# Control.net
KiCad netlist of a schematic drawn in Altium Designer
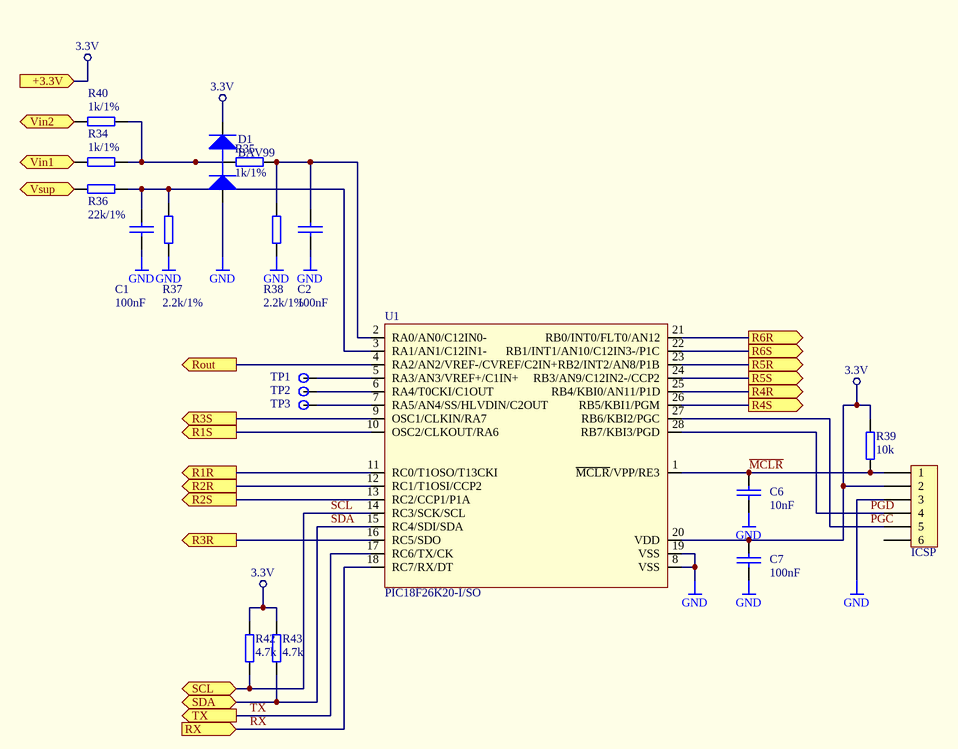
[diagram p0: Control.SchDoc]

(export (version "E")
  (design (tool "Eeschema 10.0.6"))
  (components
    (comp (ref "C1")
      (value "100nF")
      (footprint "0805_1")
      (description "Capacitor")
      (libsource (lib "*") (part "CAP"))
    )
    (comp (ref "C2")
      (value "100nF")
      (footprint "0805_1")
      (description "Capacitor")
      (libsource (lib "*") (part "CAP"))
    )
    (comp (ref "C6")
      (value "10nF")
      (footprint "0805_1")
      (description "Capacitor")
      (libsource (lib "*") (part "CAP"))
    )
    (comp (ref "C7")
      (value "100nF")
      (footprint "0805_1")
      (description "Capacitor")
      (libsource (lib "*") (part "CAP"))
    )
    (comp (ref "D1")
      (value "BAV99")
      (footprint "SOT-23")
      (description "SOT23 Silicon Planar High-Speed Switching Series Diode Pair")
      (fields
        (field (name "MANUFACTURER") "Zetex")
        (field (name "PUBLISHER") "Altium Hobart Technology Centre")
      )
      (libsource (lib "Zetex Discrete Diode") (part "BAV99"))
    )
    (comp (ref "ICSP")
      (value "CON6")
      (footprint "JP6")
      (description "Connector")
      (libsource (lib "*") (part "CON6"))
    )
    (comp (ref "R34")
      (value "1k/1%")
      (footprint "0805_1")
      (description "Resistor")
      (libsource (lib "*") (part "RES"))
    )
    (comp (ref "R35")
      (value "1k/1%")
      (footprint "0805_1")
      (description "Resistor")
      (libsource (lib "*") (part "RES"))
    )
    (comp (ref "R36")
      (value "22k/1%")
      (footprint "0805_1")
      (description "Resistor")
      (libsource (lib "*") (part "RES"))
    )
    (comp (ref "R37")
      (value "2.2k/1%")
      (footprint "0805_1")
      (description "Resistor")
      (libsource (lib "*") (part "RES"))
    )
    (comp (ref "R38")
      (value "2.2k/1%")
      (footprint "0805_1")
      (description "Resistor")
      (libsource (lib "*") (part "RES"))
    )
    (comp (ref "R39")
      (value "10k")
      (footprint "0805_1")
      (description "Resistor")
      (libsource (lib "*") (part "RES"))
    )
    (comp (ref "R40")
      (value "1k/1%")
      (footprint "0805_1")
      (description "Resistor")
      (libsource (lib "*") (part "RES"))
    )
    (comp (ref "R42")
      (value "4.7k")
      (footprint "0805_1")
      (description "Resistor")
      (libsource (lib "*") (part "RES"))
    )
    (comp (ref "R43")
      (value "4.7k")
      (footprint "0805_1")
      (description "Resistor")
      (libsource (lib "*") (part "RES"))
    )
    (comp (ref "TP1")
      (value "TESTPAD")
      (footprint "PAD-36/65")
      (libsource (lib "MainSchlib") (part "TESTPAD"))
    )
    (comp (ref "TP2")
      (value "TESTPAD")
      (footprint "PAD-36/65")
      (libsource (lib "MainSchlib") (part "TESTPAD"))
    )
    (comp (ref "TP3")
      (value "TESTPAD")
      (footprint "PAD-36/65")
      (libsource (lib "MainSchlib") (part "TESTPAD"))
    )
    (comp (ref "U1")
      (value "PIC18F26K20-I/SO")
      (footprint "SOIC-28")
      (description "PIC18 mid-range mcu")
      (libsource (lib "MainSchlib") (part "PIC18F26K20-I/SO"))
    )
  )
  (nets
    (net (code "1") (name "/PGC") (class "Default")
      (node (ref "ICSP") (pin "5") (pinfunction "5_5") (pintype "passive"))
      (node (ref "U1") (pin "27") (pinfunction "RB6/KBI2/PGC_27") (pintype "passive"))
    )
    (net (code "2") (name "/PGD") (class "Default")
      (node (ref "ICSP") (pin "4") (pinfunction "4_4") (pintype "passive"))
      (node (ref "U1") (pin "28") (pinfunction "RB7/KBI3/PGD_28") (pintype "passive"))
    )
    (net (code "3") (name "/R1R") (class "Default")
      (node (ref "U1") (pin "11") (pinfunction "RC0/T1OSO/T13CKI_11") (pintype "passive"))
    )
    (net (code "4") (name "/R1S") (class "Default")
      (node (ref "U1") (pin "10") (pinfunction "OSC2/CLKOUT/RA6_10") (pintype "passive"))
    )
    (net (code "5") (name "/R2R") (class "Default")
      (node (ref "U1") (pin "12") (pinfunction "RC1/T1OSI/CCP2_12") (pintype "passive"))
    )
    (net (code "6") (name "/R2S") (class "Default")
      (node (ref "U1") (pin "13") (pinfunction "RC2/CCP1/P1A_13") (pintype "passive"))
    )
    (net (code "7") (name "/R3R") (class "Default")
      (node (ref "U1") (pin "16") (pinfunction "RC5/SDO_16") (pintype "passive"))
    )
    (net (code "8") (name "/R3S") (class "Default")
      (node (ref "U1") (pin "9") (pinfunction "OSC1/CLKIN/RA7_9") (pintype "passive"))
    )
    (net (code "9") (name "/R4R") (class "Default")
      (node (ref "U1") (pin "25") (pinfunction "RB4/KBI0/AN11/P1D_25") (pintype "passive"))
    )
    (net (code "10") (name "/R4S") (class "Default")
      (node (ref "U1") (pin "26") (pinfunction "RB5/KBI1/PGM_26") (pintype "passive"))
    )
    (net (code "11") (name "/R5R") (class "Default")
      (node (ref "U1") (pin "23") (pinfunction "RB2/INT2/AN8/P1B_23") (pintype "passive"))
    )
    (net (code "12") (name "/R5S") (class "Default")
      (node (ref "U1") (pin "24") (pinfunction "RB3/AN9/C12IN2-/CCP2_24") (pintype "passive"))
    )
    (net (code "13") (name "/R6R") (class "Default")
      (node (ref "U1") (pin "21") (pinfunction "RB0/INT0/FLT0/AN12_21") (pintype "passive"))
    )
    (net (code "14") (name "/R6S") (class "Default")
      (node (ref "U1") (pin "22") (pinfunction "RB1/INT1/AN10/C12IN3-/P1C_22") (pintype "passive"))
    )
    (net (code "15") (name "/RX") (class "Default")
      (node (ref "U1") (pin "18") (pinfunction "RC7/RX/DT_18") (pintype "passive"))
    )
    (net (code "16") (name "/Rout") (class "Default")
      (node (ref "U1") (pin "4") (pinfunction "RA2/AN2/VREF-/CVREF/C2IN+_4") (pintype "passive"))
    )
    (net (code "17") (name "/SCL") (class "Default")
      (node (ref "R42") (pin "1") (pintype "passive"))
      (node (ref "U1") (pin "14") (pinfunction "RC3/SCK/SCL_14") (pintype "passive"))
    )
    (net (code "18") (name "/SDA") (class "Default")
      (node (ref "R43") (pin "1") (pintype "passive"))
      (node (ref "U1") (pin "15") (pinfunction "RC4/SDI/SDA_15") (pintype "passive"))
    )
    (net (code "19") (name "/TX") (class "Default")
      (node (ref "U1") (pin "17") (pinfunction "RC6/TX/CK_17") (pintype "passive"))
    )
    (net (code "20") (name "/Vin1") (class "Default") (node (ref "R34") (pin "2") (pintype "passive")))
    (net (code "21") (name "/Vin2") (class "Default") (node (ref "R40") (pin "2") (pintype "passive")))
    (net (code "22") (name "/Vsup") (class "Default") (node (ref "R36") (pin "2") (pintype "passive")))
    (net (code "23") (name "/~{MCLR}") (class "Default")
      (node (ref "C6") (pin "1") (pinfunction "1_1") (pintype "passive"))
      (node (ref "ICSP") (pin "1") (pinfunction "1_1") (pintype "passive"))
      (node (ref "R39") (pin "1") (pintype "passive"))
      (node (ref "U1") (pin "1") (pinfunction "~{MCLR}/VPP/RE3_1") (pintype "passive"))
    )
    (net (code "24") (name "3.3V") (class "Default")
      (node (ref "C7") (pin "1") (pinfunction "1_1") (pintype "passive"))
      (node (ref "D1") (pin "2") (pinfunction "K_2") (pintype "passive"))
      (node (ref "ICSP") (pin "2") (pinfunction "2_2") (pintype "passive"))
      (node (ref "R39") (pin "2") (pintype "passive"))
      (node (ref "R42") (pin "2") (pintype "passive"))
      (node (ref "R43") (pin "2") (pintype "passive"))
      (node (ref "U1") (pin "20") (pinfunction "VDD_20") (pintype "passive"))
    )
    (net (code "25") (name "GND") (class "Default")
      (node (ref "C1") (pin "2") (pinfunction "2_2") (pintype "passive"))
      (node (ref "C2") (pin "2") (pinfunction "2_2") (pintype "passive"))
      (node (ref "C6") (pin "2") (pinfunction "2_2") (pintype "passive"))
      (node (ref "C7") (pin "2") (pinfunction "2_2") (pintype "passive"))
      (node (ref "D1") (pin "1") (pinfunction "A_1") (pintype "passive"))
      (node (ref "ICSP") (pin "3") (pinfunction "3_3") (pintype "passive"))
      (node (ref "R37") (pin "1") (pintype "passive"))
      (node (ref "R38") (pin "1") (pintype "passive"))
      (node (ref "U1") (pin "19") (pinfunction "VSS_19") (pintype "passive"))
      (node (ref "U1") (pin "8") (pinfunction "VSS_8") (pintype "passive"))
    )
    (net (code "26") (name "Net-(D1-C)") (class "Default")
      (node (ref "D1") (pin "3") (pinfunction "C_3") (pintype "passive"))
      (node (ref "R34") (pin "1") (pintype "passive"))
      (node (ref "R35") (pin "2") (pintype "passive"))
      (node (ref "R40") (pin "1") (pintype "passive"))
    )
    (net (code "27") (name "Net-(U1-RA0{slash}AN0{slash}C12IN0-)") (class "Default")
      (node (ref "C2") (pin "1") (pinfunction "1_1") (pintype "passive"))
      (node (ref "R35") (pin "1") (pintype "passive"))
      (node (ref "R38") (pin "2") (pintype "passive"))
      (node (ref "U1") (pin "2") (pinfunction "RA0/AN0/C12IN0-_2") (pintype "passive"))
    )
    (net (code "28") (name "Net-(U1-RA1{slash}AN1{slash}C12IN1-)") (class "Default")
      (node (ref "C1") (pin "1") (pinfunction "1_1") (pintype "passive"))
      (node (ref "R36") (pin "1") (pintype "passive"))
      (node (ref "R37") (pin "2") (pintype "passive"))
      (node (ref "U1") (pin "3") (pinfunction "RA1/AN1/C12IN1-_3") (pintype "passive"))
    )
    (net (code "29") (name "Net-(U1-RA3{slash}AN3{slash}VREF+{slash}C1IN+)") (class "Default")
      (node (ref "TP1") (pin "1") (pinfunction "1_1") (pintype "passive"))
      (node (ref "U1") (pin "5") (pinfunction "RA3/AN3/VREF+/C1IN+_5") (pintype "passive"))
    )
    (net (code "30") (name "Net-(U1-RA4{slash}T0CKI{slash}C1OUT)") (class "Default")
      (node (ref "TP2") (pin "1") (pinfunction "1_1") (pintype "passive"))
      (node (ref "U1") (pin "6") (pinfunction "RA4/T0CKI/C1OUT_6") (pintype "passive"))
    )
    (net (code "31") (name "Net-(U1-RA5{slash}AN4{slash}SS{slash}HLVDIN{slash}C2OUT)") (class "Default")
      (node (ref "TP3") (pin "1") (pinfunction "1_1") (pintype "passive"))
      (node (ref "U1") (pin "7") (pinfunction "RA5/AN4/SS/HLVDIN/C2OUT_7") (pintype "passive"))
    )
    (net (code "32") (name "unconnected-(ICSP-Pad6)") (class "Default")
      (node (ref "ICSP") (pin "6") (pinfunction "6_6") (pintype "passive"))
    )
  )
)
